# Buck.net
KiCad netlist of a schematic drawn in Altium Designer
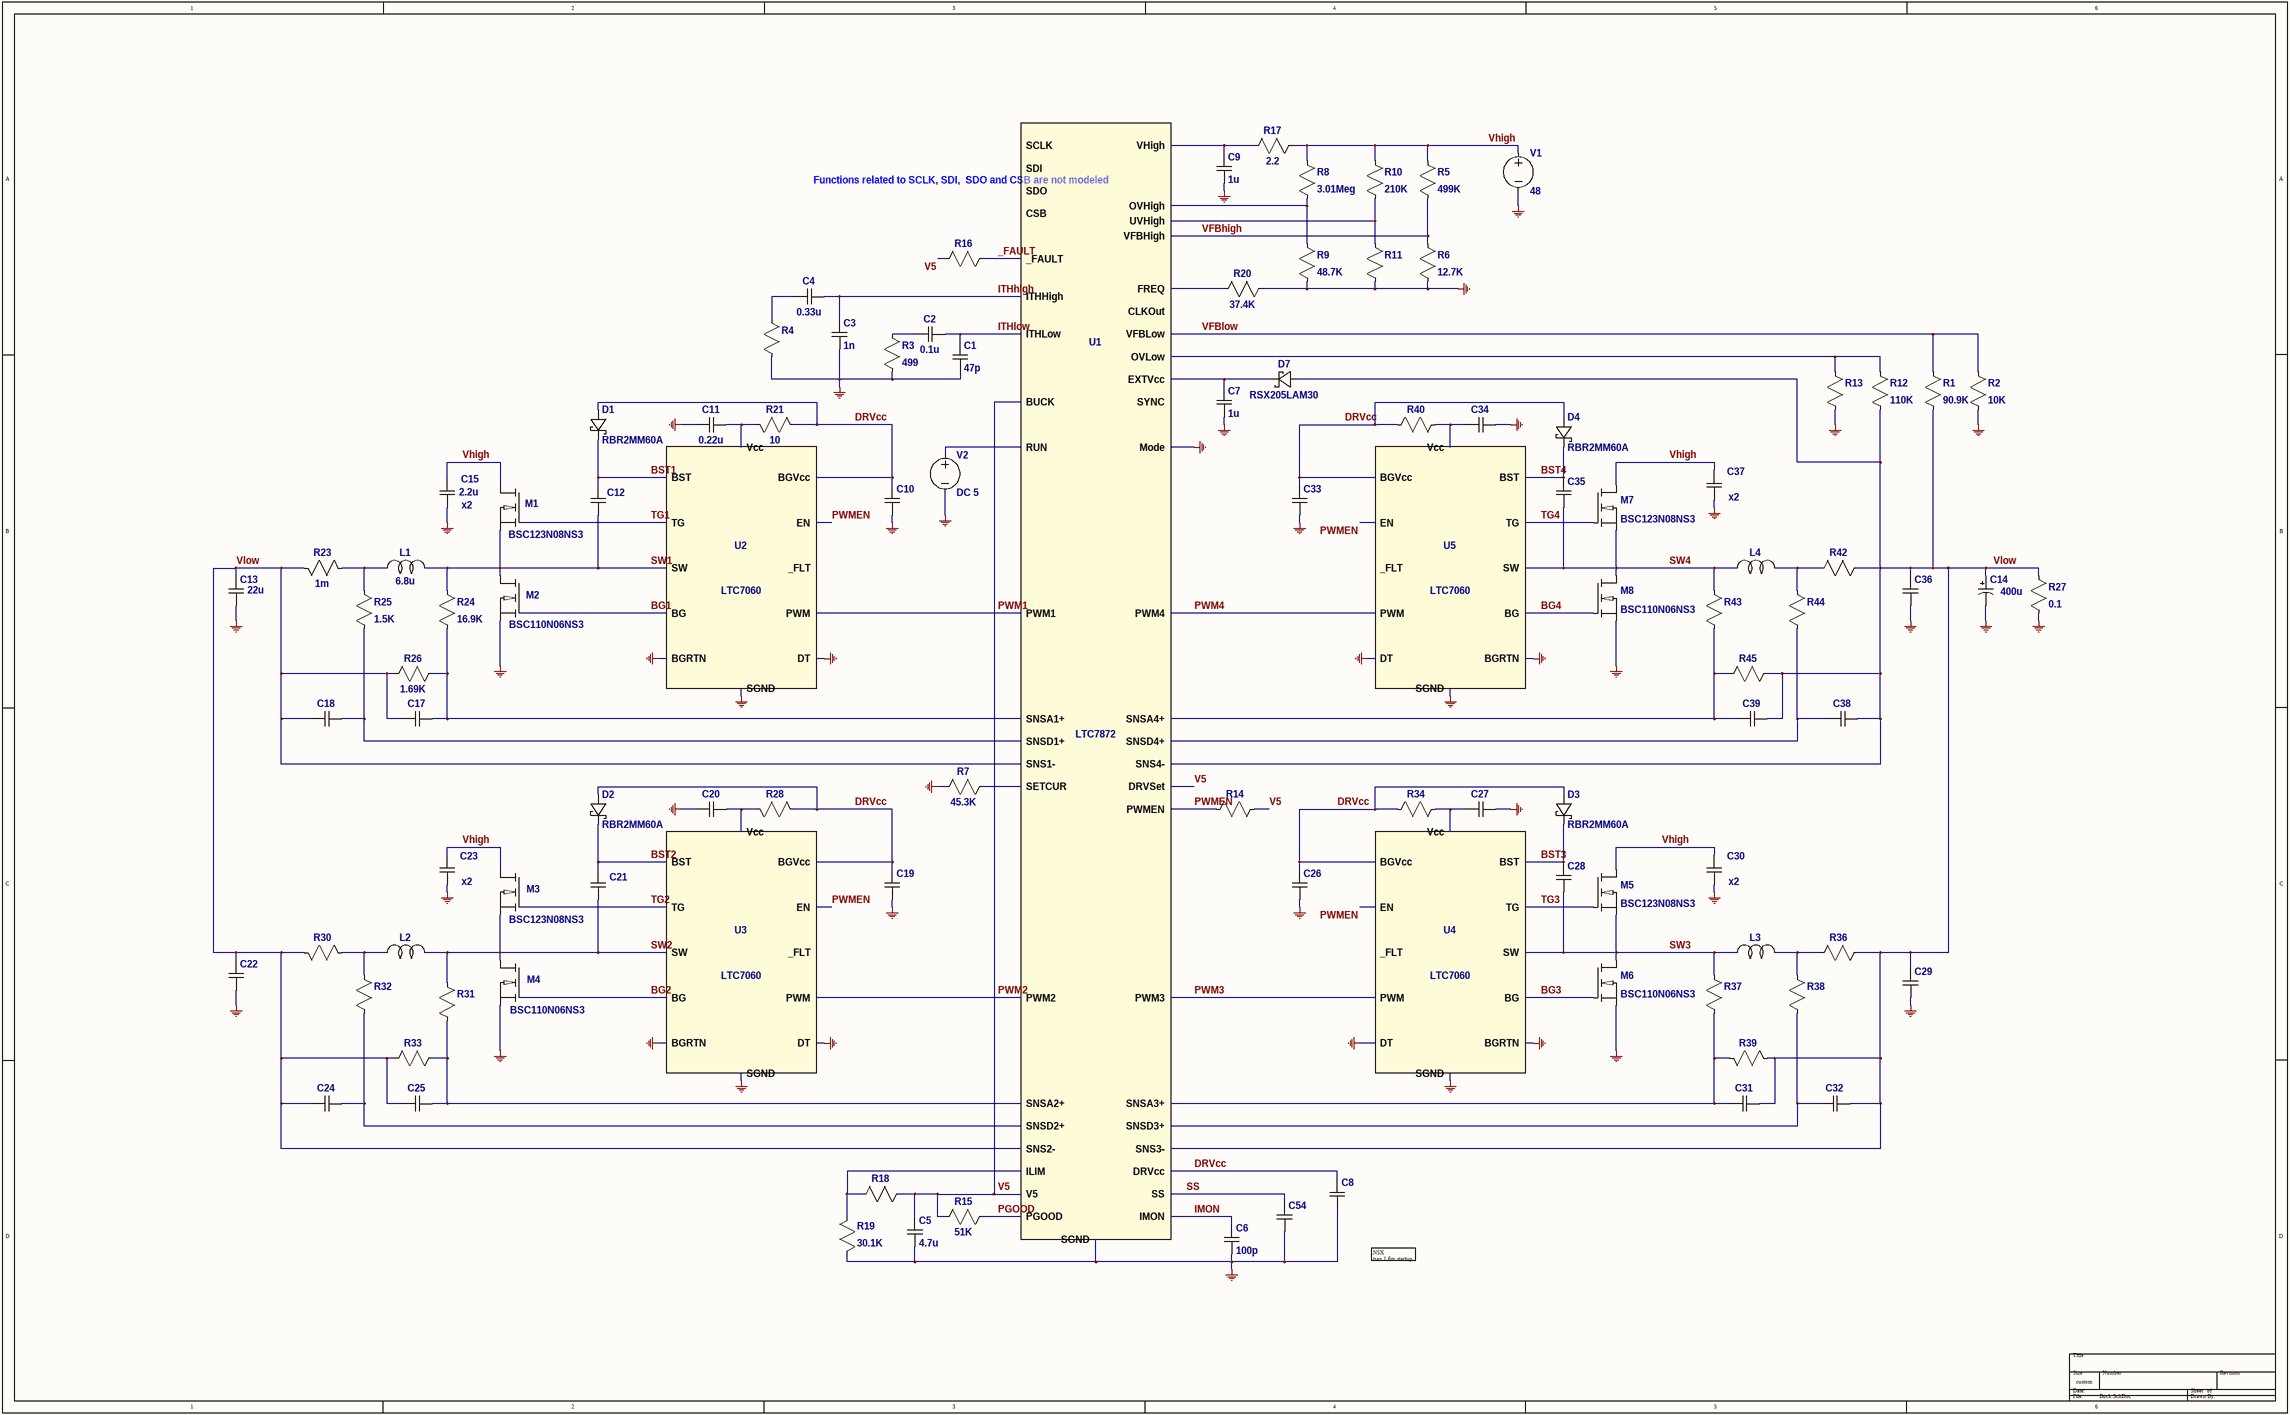
[diagram p0: Buck.SchDoc]

(export (version "E")
  (design (tool "Eeschema 10.0.6"))
  (components
    (comp (ref "C1") (value "47p") (libsource (lib "LTSpiceLibrary") (part "cap-47p")))
    (comp (ref "C2") (value "0.1u") (libsource (lib "") (part "cap-0.1u_6")))
    (comp (ref "C3") (value "1n") (libsource (lib "") (part "cap-1n_1")))
    (comp (ref "C4") (value "0.33u") (libsource (lib "LTSpiceLibrary") (part "cap-0.33u")))
    (comp (ref "C5") (value "4.7u") (libsource (lib "LTSpiceLibrary") (part "cap-4.7u")))
    (comp (ref "C6") (value "100p") (libsource (lib "LTSpiceLibrary") (part "cap-100p")))
    (comp (ref "C7") (value "1u") (libsource (lib "") (part "cap-1u_3")))
    (comp (ref "C8") (value "4.7u") (libsource (lib "") (part "cap-4.7u_1")))
    (comp (ref "C9") (value "1u") (libsource (lib "") (part "cap-1u_2")))
    (comp (ref "C10") (value "1u") (libsource (lib "") (part "cap-1u_4")))
    (comp (ref "C11") (value "0.22u") (libsource (lib "") (part "cap-0.22u_2")))
    (comp (ref "C12") (value "0.22u") (libsource (lib "") (part "cap-0.22u_3")))
    (comp (ref "C13") (value "22u") (libsource (lib "LTSpiceLibrary") (part "cap-22u")))
    (comp (ref "C14")
      (value "400u")
      (description "Capacitor")
      (libsource (lib "LTSpiceLibrary") (part "polcap-400u"))
    )
    (comp (ref "C15")
      (value "2.2u")
      (fields (field (name "VALUE2") "x2"))
      (libsource (lib "LTSpiceLibrary") (part "cap-2.2u"))
    )
    (comp (ref "C17") (value "0.1u") (libsource (lib "LTSpiceLibrary") (part "cap-0.1u")))
    (comp (ref "C18") (value "0.1u") (libsource (lib "") (part "cap-0.1u_2")))
    (comp (ref "C19") (value "1u") (libsource (lib "") (part "cap-1u_1")))
    (comp (ref "C20") (value "0.22u") (libsource (lib "") (part "cap-0.22u_2")))
    (comp (ref "C21") (value "0.22u") (libsource (lib "") (part "cap-0.22u_4")))
    (comp (ref "C22") (value "22u") (libsource (lib "") (part "cap-22u_2")))
    (comp (ref "C23")
      (value "2.2u")
      (fields (field (name "VALUE2") "x2"))
      (libsource (lib "LTSpiceLibrary") (part "cap-2.2u"))
    )
    (comp (ref "C24") (value "0.1u") (libsource (lib "") (part "cap-0.1u_4")))
    (comp (ref "C25") (value "0.1u") (libsource (lib "") (part "cap-0.1u_3")))
    (comp (ref "C26") (value "1u") (libsource (lib "") (part "cap-1u_2")))
    (comp (ref "C27") (value "0.22u") (libsource (lib "") (part "cap-0.22u_2")))
    (comp (ref "C28") (value "0.22u") (libsource (lib "LTSpiceLibrary") (part "cap-0.22u")))
    (comp (ref "C29") (value "22u") (libsource (lib "") (part "cap-22u_3")))
    (comp (ref "C30")
      (value "2.2u")
      (fields (field (name "VALUE2") "x2"))
      (libsource (lib "") (part "cap-2.2u_1"))
    )
    (comp (ref "C31") (value "0.1u") (libsource (lib "") (part "cap-0.1u_1")))
    (comp (ref "C32") (value "0.1u") (libsource (lib "") (part "cap-0.1u_4")))
    (comp (ref "C33") (value "1u") (libsource (lib "LTSpiceLibrary") (part "cap-1u")))
    (comp (ref "C34") (value "0.22u") (libsource (lib "") (part "cap-0.22u_2")))
    (comp (ref "C35") (value "0.22u") (libsource (lib "") (part "cap-0.22u_1")))
    (comp (ref "C36") (value "22u") (libsource (lib "") (part "cap-22u_1")))
    (comp (ref "C37")
      (value "2.2u")
      (fields (field (name "VALUE2") "x2"))
      (libsource (lib "") (part "cap-2.2u_1"))
    )
    (comp (ref "C38") (value "0.1u") (libsource (lib "") (part "cap-0.1u_5")))
    (comp (ref "C39") (value "0.1u") (libsource (lib "") (part "cap-0.1u_2")))
    (comp (ref "C54") (value "1n") (libsource (lib "LTSpiceLibrary") (part "cap-1n")))
    (comp (ref "D1")
      (value "RBR2MM60A")
      (description "Diode")
      (libsource (lib "") (part "schottky-RBR2MM60A_1"))
    )
    (comp (ref "D2")
      (value "RBR2MM60A")
      (description "Diode")
      (libsource (lib "") (part "schottky-RBR2MM60A_2"))
    )
    (comp (ref "D3")
      (value "RBR2MM60A")
      (description "Diode")
      (libsource (lib "LTSpiceLibrary") (part "schottky-RBR2MM60A"))
    )
    (comp (ref "D4")
      (value "RBR2MM60A")
      (description "Diode")
      (libsource (lib "LTSpiceLibrary") (part "schottky-RBR2MM60A"))
    )
    (comp (ref "D7")
      (value "RSX205LAM30")
      (description "Diode")
      (libsource (lib "LTSpiceLibrary") (part "schottky-RSX205LAM30"))
    )
    (comp (ref "L1") (value "6.8u") (libsource (lib "LTSpiceLibrary") (part "ind-6.8u")))
    (comp (ref "L2") (value "6.8u") (libsource (lib "LTSpiceLibrary") (part "ind-6.8u")))
    (comp (ref "L3") (value "6.8u") (libsource (lib "") (part "ind-6.8u_1")))
    (comp (ref "L4") (value "6.8u") (libsource (lib "") (part "ind-6.8u_1")))
    (comp (ref "M1") (value "BSC123N08NS3") (libsource (lib "") (part "NMOS-BSC123N08NS3_1")))
    (comp (ref "M2") (value "BSC110N06NS3") (libsource (lib "") (part "NMOS-BSC110N06NS3_1")))
    (comp (ref "M3") (value "BSC123N08NS3") (libsource (lib "LTSpiceLibrary") (part "NMOS-BSC123N08NS3")))
    (comp (ref "M4") (value "BSC110N06NS3") (libsource (lib "LTSpiceLibrary") (part "NMOS-BSC110N06NS3")))
    (comp (ref "M5") (value "BSC123N08NS3") (libsource (lib "LTSpiceLibrary") (part "NMOS-BSC123N08NS3")))
    (comp (ref "M6") (value "BSC110N06NS3") (libsource (lib "LTSpiceLibrary") (part "NMOS-BSC110N06NS3")))
    (comp (ref "M7") (value "BSC123N08NS3") (libsource (lib "") (part "NMOS-BSC123N08NS3_1")))
    (comp (ref "M8") (value "BSC110N06NS3") (libsource (lib "") (part "NMOS-BSC110N06NS3_1")))
    (comp (ref "R1") (value "90.9K") (libsource (lib "LTSpiceLibrary") (part "res-90.9K")))
    (comp (ref "R2") (value "10K") (libsource (lib "") (part "res-10K_2")))
    (comp (ref "R3") (value "499") (libsource (lib "LTSpiceLibrary") (part "res-499")))
    (comp (ref "R4") (value "499") (libsource (lib "") (part "res-499_1")))
    (comp (ref "R5") (value "499K") (libsource (lib "LTSpiceLibrary") (part "res-499K")))
    (comp (ref "R6") (value "12.7K") (libsource (lib "LTSpiceLibrary") (part "res-12.7K")))
    (comp (ref "R7") (value "45.3K") (libsource (lib "LTSpiceLibrary") (part "res-45.3K")))
    (comp (ref "R8") (value "3.01Meg") (libsource (lib "LTSpiceLibrary") (part "res-3.01Meg")))
    (comp (ref "R9") (value "48.7K") (libsource (lib "LTSpiceLibrary") (part "res-48.7K")))
    (comp (ref "R10") (value "210K") (libsource (lib "LTSpiceLibrary") (part "res-210K")))
    (comp (ref "R11") (value "10K") (libsource (lib "") (part "res-10K_3")))
    (comp (ref "R12") (value "110K") (libsource (lib "LTSpiceLibrary") (part "res-110K")))
    (comp (ref "R13") (value "10K") (libsource (lib "") (part "res-10K_1")))
    (comp (ref "R14") (value "10K") (libsource (lib "LTSpiceLibrary") (part "res-10K")))
    (comp (ref "R15") (value "51K") (libsource (lib "") (part "res-51K_1")))
    (comp (ref "R16") (value "51K") (libsource (lib "LTSpiceLibrary") (part "res-51K")))
    (comp (ref "R17") (value "2.2") (libsource (lib "LTSpiceLibrary") (part "res-2.2")))
    (comp (ref "R18") (value "10K") (libsource (lib "LTSpiceLibrary") (part "res-10K")))
    (comp (ref "R19") (value "30.1K") (libsource (lib "LTSpiceLibrary") (part "res-30.1K")))
    (comp (ref "R20") (value "37.4K") (libsource (lib "LTSpiceLibrary") (part "res-37.4K")))
    (comp (ref "R21") (value "10") (libsource (lib "LTSpiceLibrary") (part "res-10")))
    (comp (ref "R23") (value "1m") (libsource (lib "") (part "res-1m_2")))
    (comp (ref "R24") (value "16.9K") (libsource (lib "LTSpiceLibrary") (part "res-16.9K")))
    (comp (ref "R25") (value "1.5K") (libsource (lib "") (part "res-1.5K_1")))
    (comp (ref "R26") (value "1.69K") (libsource (lib "") (part "res-1.69K_2")))
    (comp (ref "R27") (value "0.1") (libsource (lib "LTSpiceLibrary") (part "res-0.1")))
    (comp (ref "R28") (value "10") (libsource (lib "LTSpiceLibrary") (part "res-10")))
    (comp (ref "R30") (value "1m") (libsource (lib "") (part "res-1m_3")))
    (comp (ref "R31") (value "16.9K") (libsource (lib "") (part "res-16.9K_2")))
    (comp (ref "R32") (value "1.5K") (libsource (lib "LTSpiceLibrary") (part "res-1.5K")))
    (comp (ref "R33") (value "1.69K") (libsource (lib "") (part "res-1.69K_3")))
    (comp (ref "R34") (value "10") (libsource (lib "LTSpiceLibrary") (part "res-10")))
    (comp (ref "R36") (value "1m") (libsource (lib "LTSpiceLibrary") (part "res-1m")))
    (comp (ref "R37") (value "16.9K") (libsource (lib "") (part "res-16.9K_1")))
    (comp (ref "R38") (value "1.5K") (libsource (lib "LTSpiceLibrary") (part "res-1.5K")))
    (comp (ref "R39") (value "1.69K") (libsource (lib "LTSpiceLibrary") (part "res-1.69K")))
    (comp (ref "R40") (value "10") (libsource (lib "LTSpiceLibrary") (part "res-10")))
    (comp (ref "R42") (value "1m") (libsource (lib "") (part "res-1m_1")))
    (comp (ref "R43") (value "16.9K") (libsource (lib "") (part "res-16.9K_3")))
    (comp (ref "R44") (value "1.5K") (libsource (lib "") (part "res-1.5K_1")))
    (comp (ref "R45") (value "1.69K") (libsource (lib "") (part "res-1.69K_1")))
    (comp (ref "U1")
      (value "LTC7872")
      (footprint "LXE_05-08-1832_ADI")
      (libsource (lib "LTSpiceLibrary") (part "LTC7872"))
    )
    (comp (ref "U2") (value "LTC7060") (footprint "MSOP12_MSE_ADI") (libsource (lib "") (part "LTC7060_2")))
    (comp (ref "U3") (value "LTC7060") (footprint "MSOP12_MSE_ADI") (libsource (lib "") (part "LTC7060_3")))
    (comp (ref "U4")
      (value "LTC7060")
      (footprint "MSOP12_MSE_ADI")
      (libsource (lib "LTSpiceLibrary") (part "LTC7060"))
    )
    (comp (ref "U5") (value "LTC7060") (footprint "MSOP12_MSE_ADI") (libsource (lib "") (part "LTC7060_1")))
    (comp (ref "V1")
      (value "48")
      (description "voltage source")
      (libsource (lib "LTSpiceLibrary") (part "voltage-48"))
    )
    (comp (ref "V2") (value "DC 5") (description "voltage source") (libsource (lib "") (part "voltage-48_1")))
  )
  (nets
    (net (code "1") (name "/BG1") (class "Default")
      (node (ref "M2") (pin "2") (pinfunction "G_2") (pintype "passive"))
      (node (ref "U2") (pin "8") (pinfunction "BG_8") (pintype "passive"))
    )
    (net (code "2") (name "/BG2") (class "Default")
      (node (ref "M4") (pin "2") (pinfunction "G_2") (pintype "passive"))
      (node (ref "U3") (pin "8") (pinfunction "BG_8") (pintype "passive"))
    )
    (net (code "3") (name "/BG3") (class "Default")
      (node (ref "M6") (pin "2") (pinfunction "G_2") (pintype "passive"))
      (node (ref "U4") (pin "8") (pinfunction "BG_8") (pintype "passive"))
    )
    (net (code "4") (name "/BG4") (class "Default")
      (node (ref "M8") (pin "2") (pinfunction "G_2") (pintype "passive"))
      (node (ref "U5") (pin "8") (pinfunction "BG_8") (pintype "passive"))
    )
    (net (code "5") (name "/BST1") (class "Default")
      (node (ref "C12") (pin "1") (pinfunction "A_1") (pintype "passive"))
      (node (ref "D1") (pin "2") (pinfunction "-_2") (pintype "passive"))
      (node (ref "U2") (pin "11") (pinfunction "BST_11") (pintype "passive"))
    )
    (net (code "6") (name "/BST2") (class "Default")
      (node (ref "C21") (pin "1") (pinfunction "A_1") (pintype "passive"))
      (node (ref "D2") (pin "2") (pinfunction "-_2") (pintype "passive"))
      (node (ref "U3") (pin "11") (pinfunction "BST_11") (pintype "passive"))
    )
    (net (code "7") (name "/BST3") (class "Default")
      (node (ref "C28") (pin "1") (pinfunction "A_1") (pintype "passive"))
      (node (ref "D3") (pin "2") (pinfunction "-_2") (pintype "passive"))
      (node (ref "U4") (pin "11") (pinfunction "BST_11") (pintype "passive"))
    )
    (net (code "8") (name "/BST4") (class "Default")
      (node (ref "C35") (pin "1") (pinfunction "A_1") (pintype "passive"))
      (node (ref "D4") (pin "2") (pinfunction "-_2") (pintype "passive"))
      (node (ref "U5") (pin "11") (pinfunction "BST_11") (pintype "passive"))
    )
    (net (code "9") (name "/DRVcc") (class "Default")
      (node (ref "C10") (pin "1") (pinfunction "A_1") (pintype "passive"))
      (node (ref "C19") (pin "1") (pinfunction "A_1") (pintype "passive"))
      (node (ref "C26") (pin "1") (pinfunction "A_1") (pintype "passive"))
      (node (ref "C33") (pin "1") (pinfunction "A_1") (pintype "passive"))
      (node (ref "C8") (pin "1") (pinfunction "A_1") (pintype "passive"))
      (node (ref "D1") (pin "1") (pinfunction "+_1") (pintype "passive"))
      (node (ref "D2") (pin "1") (pinfunction "+_1") (pintype "passive"))
      (node (ref "D3") (pin "1") (pinfunction "+_1") (pintype "passive"))
      (node (ref "D4") (pin "1") (pinfunction "+_1") (pintype "passive"))
      (node (ref "R21") (pin "1") (pinfunction "A_1") (pintype "passive"))
      (node (ref "R28") (pin "1") (pinfunction "A_1") (pintype "passive"))
      (node (ref "R34") (pin "1") (pinfunction "A_1") (pintype "passive"))
      (node (ref "R40") (pin "1") (pinfunction "A_1") (pintype "passive"))
      (node (ref "U1") (pin "33") (pinfunction "DRVcc_33") (pintype "passive"))
      (node (ref "U2") (pin "6") (pinfunction "BGVcc_6") (pintype "passive"))
      (node (ref "U3") (pin "6") (pinfunction "BGVcc_6") (pintype "passive"))
      (node (ref "U4") (pin "6") (pinfunction "BGVcc_6") (pintype "passive"))
      (node (ref "U5") (pin "6") (pinfunction "BGVcc_6") (pintype "passive"))
    )
    (net (code "10") (name "/IMON") (class "Default")
      (node (ref "C6") (pin "1") (pinfunction "A_1") (pintype "passive"))
      (node (ref "U1") (pin "8") (pinfunction "IMON_8") (pintype "passive"))
    )
    (net (code "11") (name "/ITHhigh") (class "Default")
      (node (ref "C3") (pin "1") (pinfunction "A_1") (pintype "passive"))
      (node (ref "C4") (pin "1") (pinfunction "A_1") (pintype "passive"))
      (node (ref "U1") (pin "5") (pinfunction "ITHHigh_5") (pintype "passive"))
    )
    (net (code "12") (name "/ITHlow") (class "Default")
      (node (ref "C1") (pin "1") (pinfunction "A_1") (pintype "passive"))
      (node (ref "C2") (pin "1") (pinfunction "A_1") (pintype "passive"))
      (node (ref "U1") (pin "3") (pinfunction "ITHLow_3") (pintype "passive"))
    )
    (net (code "13") (name "/PGOOD") (class "Default")
      (node (ref "R15") (pin "1") (pinfunction "A_1") (pintype "passive"))
      (node (ref "U1") (pin "22") (pinfunction "PGOOD_22") (pintype "passive"))
    )
    (net (code "14") (name "/PWM1") (class "Default")
      (node (ref "U1") (pin "21") (pinfunction "PWM1_21") (pintype "passive"))
      (node (ref "U2") (pin "1") (pinfunction "PWM_1") (pintype "passive"))
    )
    (net (code "15") (name "/PWM2") (class "Default")
      (node (ref "U1") (pin "23") (pinfunction "PWM2_23") (pintype "passive"))
      (node (ref "U3") (pin "1") (pinfunction "PWM_1") (pintype "passive"))
    )
    (net (code "16") (name "/PWM3") (class "Default")
      (node (ref "U1") (pin "24") (pinfunction "PWM3_24") (pintype "passive"))
      (node (ref "U4") (pin "1") (pinfunction "PWM_1") (pintype "passive"))
    )
    (net (code "17") (name "/PWM4") (class "Default")
      (node (ref "U1") (pin "26") (pinfunction "PWM4_26") (pintype "passive"))
      (node (ref "U5") (pin "1") (pinfunction "PWM_1") (pintype "passive"))
    )
    (net (code "18") (name "/PWMEN") (class "Default")
      (node (ref "R14") (pin "1") (pinfunction "A_1") (pintype "passive"))
      (node (ref "U1") (pin "20") (pinfunction "PWMEN_20") (pintype "passive"))
      (node (ref "U2") (pin "2") (pinfunction "EN_2") (pintype "passive"))
      (node (ref "U3") (pin "2") (pinfunction "EN_2") (pintype "passive"))
      (node (ref "U4") (pin "2") (pinfunction "EN_2") (pintype "passive"))
      (node (ref "U5") (pin "2") (pinfunction "EN_2") (pintype "passive"))
    )
    (net (code "19") (name "/SS") (class "Default")
      (node (ref "C54") (pin "1") (pinfunction "A_1") (pintype "passive"))
      (node (ref "U1") (pin "1") (pinfunction "SS_1") (pintype "passive"))
    )
    (net (code "20") (name "/SW1") (class "Default")
      (node (ref "C12") (pin "2") (pinfunction "B_2") (pintype "passive"))
      (node (ref "L1") (pin "1") (pinfunction "A_1") (pintype "passive"))
      (node (ref "M1") (pin "3") (pinfunction "S_3") (pintype "passive"))
      (node (ref "M2") (pin "1") (pinfunction "D_1") (pintype "passive"))
      (node (ref "R24") (pin "1") (pinfunction "A_1") (pintype "passive"))
      (node (ref "U2") (pin "9") (pinfunction "SW_9") (pintype "passive"))
    )
    (net (code "21") (name "/SW2") (class "Default")
      (node (ref "C21") (pin "2") (pinfunction "B_2") (pintype "passive"))
      (node (ref "L2") (pin "1") (pinfunction "A_1") (pintype "passive"))
      (node (ref "M3") (pin "3") (pinfunction "S_3") (pintype "passive"))
      (node (ref "M4") (pin "1") (pinfunction "D_1") (pintype "passive"))
      (node (ref "R31") (pin "1") (pinfunction "A_1") (pintype "passive"))
      (node (ref "U3") (pin "9") (pinfunction "SW_9") (pintype "passive"))
    )
    (net (code "22") (name "/SW3") (class "Default")
      (node (ref "C28") (pin "2") (pinfunction "B_2") (pintype "passive"))
      (node (ref "L3") (pin "1") (pinfunction "A_1") (pintype "passive"))
      (node (ref "M5") (pin "3") (pinfunction "S_3") (pintype "passive"))
      (node (ref "M6") (pin "1") (pinfunction "D_1") (pintype "passive"))
      (node (ref "R37") (pin "1") (pinfunction "A_1") (pintype "passive"))
      (node (ref "U4") (pin "9") (pinfunction "SW_9") (pintype "passive"))
    )
    (net (code "23") (name "/SW4") (class "Default")
      (node (ref "C35") (pin "2") (pinfunction "B_2") (pintype "passive"))
      (node (ref "L4") (pin "1") (pinfunction "A_1") (pintype "passive"))
      (node (ref "M7") (pin "3") (pinfunction "S_3") (pintype "passive"))
      (node (ref "M8") (pin "1") (pinfunction "D_1") (pintype "passive"))
      (node (ref "R43") (pin "1") (pinfunction "A_1") (pintype "passive"))
      (node (ref "U5") (pin "9") (pinfunction "SW_9") (pintype "passive"))
    )
    (net (code "24") (name "/TG1") (class "Default")
      (node (ref "M1") (pin "2") (pinfunction "G_2") (pintype "passive"))
      (node (ref "U2") (pin "10") (pinfunction "TG_10") (pintype "passive"))
    )
    (net (code "25") (name "/TG2") (class "Default")
      (node (ref "M3") (pin "2") (pinfunction "G_2") (pintype "passive"))
      (node (ref "U3") (pin "10") (pinfunction "TG_10") (pintype "passive"))
    )
    (net (code "26") (name "/TG3") (class "Default")
      (node (ref "M5") (pin "2") (pinfunction "G_2") (pintype "passive"))
      (node (ref "U4") (pin "10") (pinfunction "TG_10") (pintype "passive"))
    )
    (net (code "27") (name "/TG4") (class "Default")
      (node (ref "M7") (pin "2") (pinfunction "G_2") (pintype "passive"))
      (node (ref "U5") (pin "10") (pinfunction "TG_10") (pintype "passive"))
    )
    (net (code "28") (name "/V5") (class "Default")
      (node (ref "C5") (pin "1") (pinfunction "A_1") (pintype "passive"))
      (node (ref "R14") (pin "2") (pinfunction "B_2") (pintype "passive"))
      (node (ref "R15") (pin "2") (pinfunction "B_2") (pintype "passive"))
      (node (ref "R16") (pin "2") (pinfunction "B_2") (pintype "passive"))
      (node (ref "R18") (pin "1") (pinfunction "A_1") (pintype "passive"))
      (node (ref "U1") (pin "32") (pinfunction "DRVSet_32") (pintype "passive"))
      (node (ref "U1") (pin "40") (pinfunction "BUCK_40") (pintype "passive"))
      (node (ref "U1") (pin "7") (pinfunction "V5_7") (pintype "passive"))
    )
    (net (code "29") (name "/VFBhigh") (class "Default")
      (node (ref "R5") (pin "2") (pinfunction "B_2") (pintype "passive"))
      (node (ref "R6") (pin "1") (pinfunction "A_1") (pintype "passive"))
      (node (ref "U1") (pin "6") (pinfunction "VFBHigh_6") (pintype "passive"))
    )
    (net (code "30") (name "/VFBlow") (class "Default")
      (node (ref "R1") (pin "1") (pinfunction "A_1") (pintype "passive"))
      (node (ref "R2") (pin "1") (pinfunction "A_1") (pintype "passive"))
      (node (ref "U1") (pin "2") (pinfunction "VFBLow_2") (pintype "passive"))
    )
    (net (code "31") (name "/Vhigh") (class "Default")
      (node (ref "C15") (pin "1") (pinfunction "A_1") (pintype "passive"))
      (node (ref "C23") (pin "1") (pinfunction "A_1") (pintype "passive"))
      (node (ref "C30") (pin "1") (pinfunction "A_1") (pintype "passive"))
      (node (ref "C37") (pin "1") (pinfunction "A_1") (pintype "passive"))
      (node (ref "M1") (pin "1") (pinfunction "D_1") (pintype "passive"))
      (node (ref "M3") (pin "1") (pinfunction "D_1") (pintype "passive"))
      (node (ref "M5") (pin "1") (pinfunction "D_1") (pintype "passive"))
      (node (ref "M7") (pin "1") (pinfunction "D_1") (pintype "passive"))
      (node (ref "R10") (pin "1") (pinfunction "A_1") (pintype "passive"))
      (node (ref "R17") (pin "1") (pinfunction "A_1") (pintype "passive"))
      (node (ref "R5") (pin "1") (pinfunction "A_1") (pintype "passive"))
      (node (ref "R8") (pin "1") (pinfunction "A_1") (pintype "passive"))
      (node (ref "V1") (pin "1") (pinfunction "+_1") (pintype "passive"))
    )
    (net (code "32") (name "/Vlow") (class "Default")
      (node (ref "C13") (pin "1") (pinfunction "A_1") (pintype "passive"))
      (node (ref "C14") (pin "1") (pinfunction "A_1") (pintype "passive"))
      (node (ref "C17") (pin "2") (pinfunction "B_2") (pintype "passive"))
      (node (ref "C18") (pin "2") (pinfunction "B_2") (pintype "passive"))
      (node (ref "C22") (pin "1") (pinfunction "A_1") (pintype "passive"))
      (node (ref "C24") (pin "2") (pinfunction "B_2") (pintype "passive"))
      (node (ref "C25") (pin "2") (pinfunction "B_2") (pintype "passive"))
      (node (ref "C29") (pin "1") (pinfunction "A_1") (pintype "passive"))
      (node (ref "C31") (pin "2") (pinfunction "B_2") (pintype "passive"))
      (node (ref "C32") (pin "2") (pinfunction "B_2") (pintype "passive"))
      (node (ref "C36") (pin "1") (pinfunction "A_1") (pintype "passive"))
      (node (ref "C38") (pin "1") (pinfunction "A_1") (pintype "passive"))
      (node (ref "C39") (pin "1") (pinfunction "A_1") (pintype "passive"))
      (node (ref "D7") (pin "1") (pinfunction "+_1") (pintype "passive"))
      (node (ref "R1") (pin "2") (pinfunction "B_2") (pintype "passive"))
      (node (ref "R12") (pin "2") (pinfunction "B_2") (pintype "passive"))
      (node (ref "R23") (pin "1") (pinfunction "A_1") (pintype "passive"))
      (node (ref "R26") (pin "2") (pinfunction "B_2") (pintype "passive"))
      (node (ref "R27") (pin "1") (pinfunction "A_1") (pintype "passive"))
      (node (ref "R30") (pin "1") (pinfunction "A_1") (pintype "passive"))
      (node (ref "R33") (pin "2") (pinfunction "B_2") (pintype "passive"))
      (node (ref "R36") (pin "1") (pinfunction "A_1") (pintype "passive"))
      (node (ref "R39") (pin "2") (pinfunction "B_2") (pintype "passive"))
      (node (ref "R42") (pin "1") (pinfunction "A_1") (pintype "passive"))
      (node (ref "R45") (pin "1") (pinfunction "A_1") (pintype "passive"))
      (node (ref "U1") (pin "14") (pinfunction "SNS1-_14") (pintype "passive"))
      (node (ref "U1") (pin "17") (pinfunction "SNS2-_17") (pintype "passive"))
      (node (ref "U1") (pin "42") (pinfunction "SNS3-_42") (pintype "passive"))
      (node (ref "U1") (pin "45") (pinfunction "SNS4-_45") (pintype "passive"))
    )
    (net (code "33") (name "/_FAULT") (class "Default")
      (node (ref "R16") (pin "1") (pinfunction "A_1") (pintype "passive"))
      (node (ref "U1") (pin "25") (pinfunction "_FAULT_25") (pintype "passive"))
    )
    (net (code "34") (name "GND") (class "Default")
      (node (ref "C1") (pin "2") (pinfunction "B_2") (pintype "passive"))
      (node (ref "C10") (pin "2") (pinfunction "B_2") (pintype "passive"))
      (node (ref "C11") (pin "2") (pinfunction "B_2") (pintype "passive"))
      (node (ref "C13") (pin "2") (pinfunction "B_2") (pintype "passive"))
      (node (ref "C14") (pin "2") (pinfunction "B_2") (pintype "passive"))
      (node (ref "C15") (pin "2") (pinfunction "B_2") (pintype "passive"))
      (node (ref "C19") (pin "2") (pinfunction "B_2") (pintype "passive"))
      (node (ref "C20") (pin "2") (pinfunction "B_2") (pintype "passive"))
      (node (ref "C22") (pin "2") (pinfunction "B_2") (pintype "passive"))
      (node (ref "C23") (pin "2") (pinfunction "B_2") (pintype "passive"))
      (node (ref "C26") (pin "2") (pinfunction "B_2") (pintype "passive"))
      (node (ref "C27") (pin "2") (pinfunction "B_2") (pintype "passive"))
      (node (ref "C29") (pin "2") (pinfunction "B_2") (pintype "passive"))
      (node (ref "C3") (pin "2") (pinfunction "B_2") (pintype "passive"))
      (node (ref "C30") (pin "2") (pinfunction "B_2") (pintype "passive"))
      (node (ref "C33") (pin "2") (pinfunction "B_2") (pintype "passive"))
      (node (ref "C34") (pin "2") (pinfunction "B_2") (pintype "passive"))
      (node (ref "C36") (pin "2") (pinfunction "B_2") (pintype "passive"))
      (node (ref "C37") (pin "2") (pinfunction "B_2") (pintype "passive"))
      (node (ref "C5") (pin "2") (pinfunction "B_2") (pintype "passive"))
      (node (ref "C54") (pin "2") (pinfunction "B_2") (pintype "passive"))
      (node (ref "C6") (pin "2") (pinfunction "B_2") (pintype "passive"))
      (node (ref "C7") (pin "2") (pinfunction "B_2") (pintype "passive"))
      (node (ref "C8") (pin "2") (pinfunction "B_2") (pintype "passive"))
      (node (ref "C9") (pin "2") (pinfunction "B_2") (pintype "passive"))
      (node (ref "M2") (pin "3") (pinfunction "S_3") (pintype "passive"))
      (node (ref "M4") (pin "3") (pinfunction "S_3") (pintype "passive"))
      (node (ref "M6") (pin "3") (pinfunction "S_3") (pintype "passive"))
      (node (ref "M8") (pin "3") (pinfunction "S_3") (pintype "passive"))
      (node (ref "R11") (pin "2") (pinfunction "B_2") (pintype "passive"))
      (node (ref "R13") (pin "2") (pinfunction "B_2") (pintype "passive"))
      (node (ref "R19") (pin "1") (pinfunction "A_1") (pintype "passive"))
      (node (ref "R2") (pin "2") (pinfunction "B_2") (pintype "passive"))
      (node (ref "R20") (pin "1") (pinfunction "A_1") (pintype "passive"))
      (node (ref "R27") (pin "2") (pinfunction "B_2") (pintype "passive"))
      (node (ref "R3") (pin "2") (pinfunction "B_2") (pintype "passive"))
      (node (ref "R4") (pin "2") (pinfunction "B_2") (pintype "passive"))
      (node (ref "R6") (pin "2") (pinfunction "B_2") (pintype "passive"))
      (node (ref "R7") (pin "2") (pinfunction "B_2") (pintype "passive"))
      (node (ref "R9") (pin "2") (pinfunction "B_2") (pintype "passive"))
      (node (ref "U1") (pin "37") (pinfunction "Mode_37") (pintype "passive"))
      (node (ref "U1") (pin "4") (pinfunction "SGND_4") (pintype "passive"))
      (node (ref "U2") (pin "12") (pinfunction "SGND_12") (pintype "passive"))
      (node (ref "U2") (pin "4") (pinfunction "DT_4") (pintype "passive"))
      (node (ref "U2") (pin "7") (pinfunction "BGRTN_7") (pintype "passive"))
      (node (ref "U3") (pin "12") (pinfunction "SGND_12") (pintype "passive"))
      (node (ref "U3") (pin "4") (pinfunction "DT_4") (pintype "passive"))
      (node (ref "U3") (pin "7") (pinfunction "BGRTN_7") (pintype "passive"))
      (node (ref "U4") (pin "12") (pinfunction "SGND_12") (pintype "passive"))
      (node (ref "U4") (pin "4") (pinfunction "DT_4") (pintype "passive"))
      (node (ref "U4") (pin "7") (pinfunction "BGRTN_7") (pintype "passive"))
      (node (ref "U5") (pin "12") (pinfunction "SGND_12") (pintype "passive"))
      (node (ref "U5") (pin "4") (pinfunction "DT_4") (pintype "passive"))
      (node (ref "U5") (pin "7") (pinfunction "BGRTN_7") (pintype "passive"))
      (node (ref "V1") (pin "2") (pinfunction "-_2") (pintype "passive"))
      (node (ref "V2") (pin "2") (pinfunction "-_2") (pintype "passive"))
    )
    (net (code "35") (name "Net-(C2-B)") (class "Default")
      (node (ref "C2") (pin "2") (pinfunction "B_2") (pintype "passive"))
      (node (ref "R3") (pin "1") (pinfunction "A_1") (pintype "passive"))
    )
    (net (code "36") (name "Net-(C4-B)") (class "Default")
      (node (ref "C4") (pin "2") (pinfunction "B_2") (pintype "passive"))
      (node (ref "R4") (pin "1") (pinfunction "A_1") (pintype "passive"))
    )
    (net (code "37") (name "Net-(C7-A)") (class "Default")
      (node (ref "C7") (pin "1") (pinfunction "A_1") (pintype "passive"))
      (node (ref "D7") (pin "2") (pinfunction "-_2") (pintype "passive"))
      (node (ref "U1") (pin "31") (pinfunction "EXTVcc_31") (pintype "passive"))
    )
    (net (code "38") (name "Net-(C9-A)") (class "Default")
      (node (ref "C9") (pin "1") (pinfunction "A_1") (pintype "passive"))
      (node (ref "R17") (pin "2") (pinfunction "B_2") (pintype "passive"))
      (node (ref "U1") (pin "34") (pinfunction "VHigh_34") (pintype "passive"))
    )
    (net (code "39") (name "Net-(C11-A)") (class "Default")
      (node (ref "C11") (pin "1") (pinfunction "A_1") (pintype "passive"))
      (node (ref "R21") (pin "2") (pinfunction "B_2") (pintype "passive"))
      (node (ref "U2") (pin "5") (pinfunction "Vcc_5") (pintype "passive"))
    )
    (net (code "40") (name "Net-(C17-A)") (class "Default")
      (node (ref "C17") (pin "1") (pinfunction "A_1") (pintype "passive"))
      (node (ref "R24") (pin "2") (pinfunction "B_2") (pintype "passive"))
      (node (ref "R26") (pin "1") (pinfunction "A_1") (pintype "passive"))
      (node (ref "U1") (pin "13") (pinfunction "SNSA1+_13") (pintype "passive"))
    )
    (net (code "41") (name "Net-(C18-A)") (class "Default")
      (node (ref "C18") (pin "1") (pinfunction "A_1") (pintype "passive"))
      (node (ref "R25") (pin "2") (pinfunction "B_2") (pintype "passive"))
      (node (ref "U1") (pin "15") (pinfunction "SNSD1+_15") (pintype "passive"))
    )
    (net (code "42") (name "Net-(C20-A)") (class "Default")
      (node (ref "C20") (pin "1") (pinfunction "A_1") (pintype "passive"))
      (node (ref "R28") (pin "2") (pinfunction "B_2") (pintype "passive"))
      (node (ref "U3") (pin "5") (pinfunction "Vcc_5") (pintype "passive"))
    )
    (net (code "43") (name "Net-(C24-A)") (class "Default")
      (node (ref "C24") (pin "1") (pinfunction "A_1") (pintype "passive"))
      (node (ref "R32") (pin "2") (pinfunction "B_2") (pintype "passive"))
      (node (ref "U1") (pin "16") (pinfunction "SNSD2+_16") (pintype "passive"))
    )
    (net (code "44") (name "Net-(C25-A)") (class "Default")
      (node (ref "C25") (pin "1") (pinfunction "A_1") (pintype "passive"))
      (node (ref "R31") (pin "2") (pinfunction "B_2") (pintype "passive"))
      (node (ref "R33") (pin "1") (pinfunction "A_1") (pintype "passive"))
      (node (ref "U1") (pin "18") (pinfunction "SNSA2+_18") (pintype "passive"))
    )
    (net (code "45") (name "Net-(C27-A)") (class "Default")
      (node (ref "C27") (pin "1") (pinfunction "A_1") (pintype "passive"))
      (node (ref "R34") (pin "2") (pinfunction "B_2") (pintype "passive"))
      (node (ref "U4") (pin "5") (pinfunction "Vcc_5") (pintype "passive"))
    )
    (net (code "46") (name "Net-(C31-A)") (class "Default")
      (node (ref "C31") (pin "1") (pinfunction "A_1") (pintype "passive"))
      (node (ref "R37") (pin "2") (pinfunction "B_2") (pintype "passive"))
      (node (ref "R39") (pin "1") (pinfunction "A_1") (pintype "passive"))
      (node (ref "U1") (pin "41") (pinfunction "SNSA3+_41") (pintype "passive"))
    )
    (net (code "47") (name "Net-(C32-A)") (class "Default")
      (node (ref "C32") (pin "1") (pinfunction "A_1") (pintype "passive"))
      (node (ref "R38") (pin "2") (pinfunction "B_2") (pintype "passive"))
      (node (ref "U1") (pin "43") (pinfunction "SNSD3+_43") (pintype "passive"))
    )
    (net (code "48") (name "Net-(C34-A)") (class "Default")
      (node (ref "C34") (pin "1") (pinfunction "A_1") (pintype "passive"))
      (node (ref "R40") (pin "2") (pinfunction "B_2") (pintype "passive"))
      (node (ref "U5") (pin "5") (pinfunction "Vcc_5") (pintype "passive"))
    )
    (net (code "49") (name "Net-(C38-B)") (class "Default")
      (node (ref "C38") (pin "2") (pinfunction "B_2") (pintype "passive"))
      (node (ref "R44") (pin "2") (pinfunction "B_2") (pintype "passive"))
      (node (ref "U1") (pin "44") (pinfunction "SNSD4+_44") (pintype "passive"))
    )
    (net (code "50") (name "Net-(C39-B)") (class "Default")
      (node (ref "C39") (pin "2") (pinfunction "B_2") (pintype "passive"))
      (node (ref "R43") (pin "2") (pinfunction "B_2") (pintype "passive"))
      (node (ref "R45") (pin "2") (pinfunction "B_2") (pintype "passive"))
      (node (ref "U1") (pin "46") (pinfunction "SNSA4+_46") (pintype "passive"))
    )
    (net (code "51") (name "Net-(L1-B)") (class "Default")
      (node (ref "L1") (pin "2") (pinfunction "B_2") (pintype "passive"))
      (node (ref "R23") (pin "2") (pinfunction "B_2") (pintype "passive"))
      (node (ref "R25") (pin "1") (pinfunction "A_1") (pintype "passive"))
    )
    (net (code "52") (name "Net-(L2-B)") (class "Default")
      (node (ref "L2") (pin "2") (pinfunction "B_2") (pintype "passive"))
      (node (ref "R30") (pin "2") (pinfunction "B_2") (pintype "passive"))
      (node (ref "R32") (pin "1") (pinfunction "A_1") (pintype "passive"))
    )
    (net (code "53") (name "Net-(L3-B)") (class "Default")
      (node (ref "L3") (pin "2") (pinfunction "B_2") (pintype "passive"))
      (node (ref "R36") (pin "2") (pinfunction "B_2") (pintype "passive"))
      (node (ref "R38") (pin "1") (pinfunction "A_1") (pintype "passive"))
    )
    (net (code "54") (name "Net-(L4-B)") (class "Default")
      (node (ref "L4") (pin "2") (pinfunction "B_2") (pintype "passive"))
      (node (ref "R42") (pin "2") (pinfunction "B_2") (pintype "passive"))
      (node (ref "R44") (pin "1") (pinfunction "A_1") (pintype "passive"))
    )
    (net (code "55") (name "Net-(R7-A)") (class "Default")
      (node (ref "R7") (pin "1") (pinfunction "A_1") (pintype "passive"))
      (node (ref "U1") (pin "9") (pinfunction "SETCUR_9") (pintype "passive"))
    )
    (net (code "56") (name "Net-(R8-B)") (class "Default")
      (node (ref "R8") (pin "2") (pinfunction "B_2") (pintype "passive"))
      (node (ref "R9") (pin "1") (pinfunction "A_1") (pintype "passive"))
      (node (ref "U1") (pin "10") (pinfunction "OVHigh_10") (pintype "passive"))
    )
    (net (code "57") (name "Net-(R10-B)") (class "Default")
      (node (ref "R10") (pin "2") (pinfunction "B_2") (pintype "passive"))
      (node (ref "R11") (pin "1") (pinfunction "A_1") (pintype "passive"))
      (node (ref "U1") (pin "11") (pinfunction "UVHigh_11") (pintype "passive"))
    )
    (net (code "58") (name "Net-(R12-A)") (class "Default")
      (node (ref "R12") (pin "1") (pinfunction "A_1") (pintype "passive"))
      (node (ref "R13") (pin "1") (pinfunction "A_1") (pintype "passive"))
      (node (ref "U1") (pin "12") (pinfunction "OVLow_12") (pintype "passive"))
    )
    (net (code "59") (name "Net-(R18-B)") (class "Default")
      (node (ref "R18") (pin "2") (pinfunction "B_2") (pintype "passive"))
      (node (ref "R19") (pin "2") (pinfunction "B_2") (pintype "passive"))
      (node (ref "U1") (pin "35") (pinfunction "ILIM_35") (pintype "passive"))
    )
    (net (code "60") (name "Net-(R20-B)") (class "Default")
      (node (ref "R20") (pin "2") (pinfunction "B_2") (pintype "passive"))
      (node (ref "U1") (pin "39") (pinfunction "FREQ_39") (pintype "passive"))
    )
    (net (code "61") (name "Net-(U1-RUN)") (class "Default")
      (node (ref "U1") (pin "19") (pinfunction "RUN_19") (pintype "passive"))
      (node (ref "V2") (pin "1") (pinfunction "+_1") (pintype "passive"))
    )
    (net (code "62") (name "unconnected-(U1-CLKOut-Pad36)") (class "Default")
      (node (ref "U1") (pin "36") (pinfunction "CLKOut_36") (pintype "passive"))
    )
    (net (code "63") (name "unconnected-(U1-CSB-Pad27)") (class "Default")
      (node (ref "U1") (pin "27") (pinfunction "CSB_27") (pintype "passive"))
    )
    (net (code "64") (name "unconnected-(U1-SCLK-Pad30)") (class "Default")
      (node (ref "U1") (pin "30") (pinfunction "SCLK_30") (pintype "passive"))
    )
    (net (code "65") (name "unconnected-(U1-SDI-Pad29)") (class "Default")
      (node (ref "U1") (pin "29") (pinfunction "SDI_29") (pintype "passive"))
    )
    (net (code "66") (name "unconnected-(U1-SDO-Pad28)") (class "Default")
      (node (ref "U1") (pin "28") (pinfunction "SDO_28") (pintype "passive"))
    )
    (net (code "67") (name "unconnected-(U1-SYNC-Pad38)") (class "Default")
      (node (ref "U1") (pin "38") (pinfunction "SYNC_38") (pintype "passive"))
    )
    (net (code "68") (name "unconnected-(U2-_FLT-Pad3)") (class "Default")
      (node (ref "U2") (pin "3") (pinfunction "_FLT_3") (pintype "passive"))
    )
    (net (code "69") (name "unconnected-(U3-_FLT-Pad3)") (class "Default")
      (node (ref "U3") (pin "3") (pinfunction "_FLT_3") (pintype "passive"))
    )
    (net (code "70") (name "unconnected-(U4-_FLT-Pad3)") (class "Default")
      (node (ref "U4") (pin "3") (pinfunction "_FLT_3") (pintype "passive"))
    )
    (net (code "71") (name "unconnected-(U5-_FLT-Pad3)") (class "Default")
      (node (ref "U5") (pin "3") (pinfunction "_FLT_3") (pintype "passive"))
    )
  )
)
